# bpod_stepper_1_4_6_teensy32.net
KiCad netlist of a schematic drawn in EAGLE
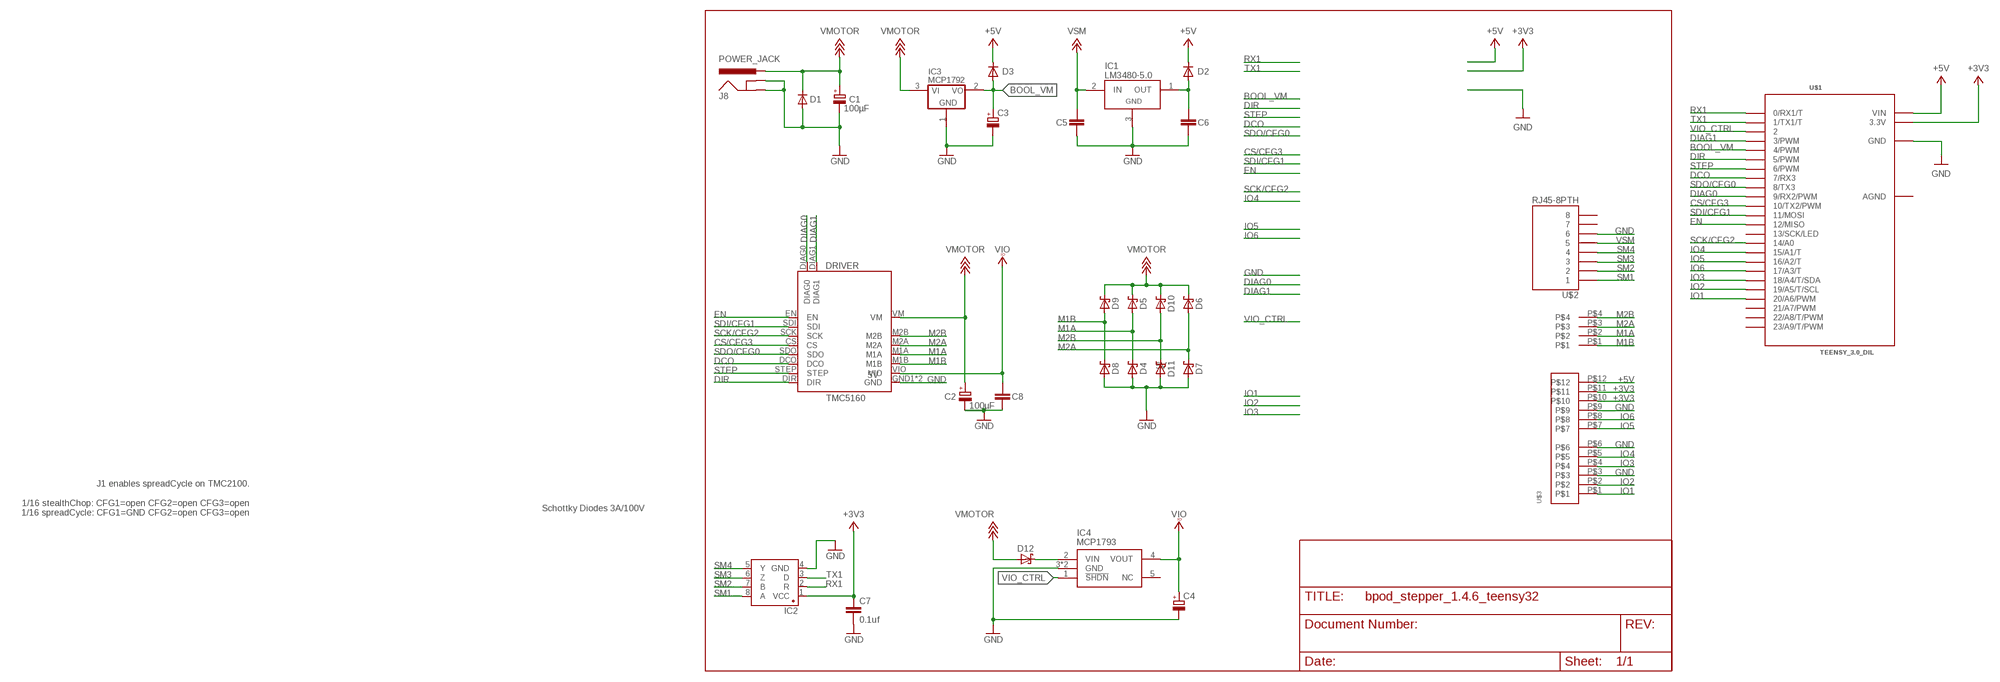
[diagram p0: schematic, sheet 1]

(export (version "E")
  (design (tool "Eeschema 10.0.6"))
  (components
    (comp (ref "C1")
      (value "100µF")
      (footprint "eagle-import:PANASONIC_G")
      (libsource (lib "eagle-import") (part "CPOL-EUG"))
    )
    (comp (ref "C2")
      (value "100µF")
      (footprint "eagle-import:PANASONIC_G")
      (libsource (lib "eagle-import") (part "CPOL-EUG"))
    )
    (comp (ref "C3")
      (value "CPOL-EUB")
      (footprint "eagle-import:PANASONIC_B")
      (libsource (lib "eagle-import") (part "CPOL-EUB"))
    )
    (comp (ref "C4")
      (value "CPOL-EUB")
      (footprint "eagle-import:PANASONIC_B")
      (libsource (lib "eagle-import") (part "CPOL-EUB"))
    )
    (comp (ref "C5")
      (value "0.1uf")
      (footprint "eagle-import:1206@1")
      (libsource (lib "eagle-import") (part "CAP1206"))
    )
    (comp (ref "C6")
      (value "0.1uf")
      (footprint "eagle-import:1206@1")
      (libsource (lib "eagle-import") (part "CAP1206"))
    )
    (comp (ref "C7")
      (value "0.1uf")
      (footprint "eagle-import:1206@1")
      (libsource (lib "eagle-import") (part "CAP1206"))
    )
    (comp (ref "C8")
      (value "100nf")
      (footprint "eagle-import:1206@1")
      (libsource (lib "eagle-import") (part "CAP1206"))
    )
    (comp (ref "D1")
      (value "DIODE-DO214AA")
      (footprint "eagle-import:DO214AA")
      (libsource (lib "eagle-import") (part "DIODE-DO214AA"))
    )
    (comp (ref "D2")
      (value "MBR0520LT")
      (footprint "eagle-import:SOD123")
      (libsource (lib "eagle-import") (part "MBR0520LT"))
    )
    (comp (ref "D3")
      (value "MBR0520LT")
      (footprint "eagle-import:SOD123")
      (libsource (lib "eagle-import") (part "MBR0520LT"))
    )
    (comp (ref "D4")
      (value "S310FA")
      (footprint "eagle-import:SOD123")
      (libsource (lib "eagle-import") (part "D_SCHOTTKY-SOD123"))
    )
    (comp (ref "D5")
      (value "S310FA")
      (footprint "eagle-import:SOD123")
      (libsource (lib "eagle-import") (part "D_SCHOTTKY-SOD123"))
    )
    (comp (ref "D6")
      (value "S310FA")
      (footprint "eagle-import:SOD123")
      (libsource (lib "eagle-import") (part "D_SCHOTTKY-SOD123"))
    )
    (comp (ref "D7")
      (value "S310FA")
      (footprint "eagle-import:SOD123")
      (libsource (lib "eagle-import") (part "D_SCHOTTKY-SOD123"))
    )
    (comp (ref "D8")
      (value "S310FA")
      (footprint "eagle-import:SOD123")
      (libsource (lib "eagle-import") (part "D_SCHOTTKY-SOD123"))
    )
    (comp (ref "D9")
      (value "S310FA")
      (footprint "eagle-import:SOD123")
      (libsource (lib "eagle-import") (part "D_SCHOTTKY-SOD123"))
    )
    (comp (ref "D10")
      (value "S310FA")
      (footprint "eagle-import:SOD123")
      (libsource (lib "eagle-import") (part "D_SCHOTTKY-SOD123"))
    )
    (comp (ref "D11")
      (value "S310FA")
      (footprint "eagle-import:SOD123")
      (libsource (lib "eagle-import") (part "D_SCHOTTKY-SOD123"))
    )
    (comp (ref "D12")
      (value "S310FA")
      (footprint "eagle-import:SOD123")
      (libsource (lib "eagle-import") (part "D_SCHOTTKY-SOD123"))
    )
    (comp (ref "DRIVER")
      (value "TMC5160")
      (footprint "eagle-import:TMC5160")
      (libsource (lib "eagle-import") (part "TMC5160"))
    )
    (comp (ref "IC1")
      (value "LM3480-5.0")
      (footprint "eagle-import:SOT-23-3")
      (libsource (lib "eagle-import") (part "LM3480-5.0"))
    )
    (comp (ref "IC2")
      (value "SN65HVD31DR")
      (footprint "eagle-import:SO08")
      (libsource (lib "eagle-import") (part "SN65HVD31DR"))
    )
    (comp (ref "IC3")
      (value "MCP1792")
      (footprint "eagle-import:SOT23A_MICROCHIP_CB")
      (libsource (lib "eagle-import") (part "MCP170302E/CB-12"))
    )
    (comp (ref "IC4")
      (value "MCP1793")
      (footprint "eagle-import:SOT223-5")
      (libsource (lib "eagle-import") (part "MCP1793_SOT223-5"))
    )
    (comp (ref "J8")
      (value "POWER_JACK")
      (footprint "eagle-import:POWER_JACK_PTH")
      (libsource (lib "eagle-import") (part "POWER_JACK"))
    )
    (comp (ref "U$1")
      (value "TEENSY_3.0_DIL")
      (footprint "eagle-import:TEENSY_3.0-3.2&LC_DIL")
      (libsource (lib "eagle-import") (part "TEENSY_3.0_DIL"))
    )
    (comp (ref "U$2")
      (value "RJ45-8PTH")
      (footprint "eagle-import:RJ45-8")
      (libsource (lib "eagle-import") (part "RJ45-8PTH"))
    )
    (comp (ref "U$3")
      (value "12POS_MOLEX_SOCKET")
      (footprint "eagle-import:12POS_MOLEX_SOCKET")
      (libsource (lib "eagle-import") (part "12POS_MOLEX_SOCKET"))
    )
    (comp (ref "U$4")
      (value "MOLEX395221004")
      (footprint "eagle-import:MOLEX395221004")
      (libsource (lib "eagle-import") (part "MOLEX395221004"))
    )
  )
  (nets
    (net (code "1") (name "+3V3") (class "Default")
      (node (ref "C7") (pin "1") (pinfunction "1_1") (pintype "passive"))
      (node (ref "IC2") (pin "1") (pinfunction "VCC_1") (pintype "bidirectional"))
      (node (ref "U$1") (pin "3.3V") (pinfunction "3.3V_3.3V") (pintype "power_in"))
      (node (ref "U$3") (pin "P$10") (pinfunction "P$10_P$10") (pintype "bidirectional"))
      (node (ref "U$3") (pin "P$11") (pinfunction "P$11_P$11") (pintype "bidirectional"))
    )
    (net (code "2") (name "+5V") (class "Default")
      (node (ref "D2") (pin "C") (pinfunction "C_C") (pintype "passive"))
      (node (ref "D3") (pin "C") (pinfunction "C_C") (pintype "passive"))
      (node (ref "U$1") (pin "VIN") (pinfunction "VIN_VIN") (pintype "power_in"))
      (node (ref "U$3") (pin "P$12") (pinfunction "P$12_P$12") (pintype "bidirectional"))
    )
    (net (code "3") (name "+12V") (class "Default")
      (node (ref "C5") (pin "2") (pinfunction "2_2") (pintype "passive"))
      (node (ref "IC1") (pin "2") (pinfunction "IN_2") (pintype "power_in"))
      (node (ref "U$2") (pin "5") (pinfunction "5_5") (pintype "bidirectional"))
    )
    (net (code "4") (name "+18V") (class "Default")
      (node (ref "C1") (pin "+") (pinfunction "+_+") (pintype "passive"))
      (node (ref "C2") (pin "+") (pinfunction "+_+") (pintype "passive"))
      (node (ref "D1") (pin "C") (pinfunction "C_C") (pintype "passive"))
      (node (ref "D10") (pin "C") (pinfunction "C_C") (pintype "passive"))
      (node (ref "D12") (pin "A") (pinfunction "A_A") (pintype "passive"))
      (node (ref "D5") (pin "C") (pinfunction "C_C") (pintype "passive"))
      (node (ref "D6") (pin "C") (pinfunction "C_C") (pintype "passive"))
      (node (ref "D9") (pin "C") (pinfunction "C_C") (pintype "passive"))
      (node (ref "DRIVER") (pin "VM") (pinfunction "VM_VM") (pintype "power_in"))
      (node (ref "IC3") (pin "3") (pinfunction "VI_3") (pintype "power_in"))
      (node (ref "J8") (pin "PWR") (pinfunction "PWR_PWR") (pintype "bidirectional"))
    )
    (net (code "5") (name "/AGND") (class "Default")
      (node (ref "U$1") (pin "AGND") (pinfunction "AGND_AGND") (pintype "power_in"))
    )
    (net (code "6") (name "/CS{slash}CFG3") (class "Default")
      (node (ref "DRIVER") (pin "CS") (pinfunction "CS_CS") (pintype "passive"))
      (node (ref "U$1") (pin "10") (pinfunction "10/TX2/PWM_10") (pintype "bidirectional"))
    )
    (net (code "7") (name "/DCO") (class "Default")
      (node (ref "DRIVER") (pin "DCO") (pinfunction "DCO_DCO") (pintype "passive"))
      (node (ref "U$1") (pin "7") (pinfunction "7/RX3_7") (pintype "bidirectional"))
    )
    (net (code "8") (name "/DIAG0") (class "Default")
      (node (ref "DRIVER") (pin "DIAG0") (pinfunction "DIAG0_DIAG0") (pintype "passive"))
      (node (ref "U$1") (pin "9") (pinfunction "9/RX2/PWM_9") (pintype "bidirectional"))
    )
    (net (code "9") (name "/DIAG1") (class "Default")
      (node (ref "DRIVER") (pin "DIAG1") (pinfunction "DIAG1_DIAG1") (pintype "passive"))
      (node (ref "U$1") (pin "3") (pinfunction "3/PWM_3") (pintype "bidirectional"))
    )
    (net (code "10") (name "/DIR") (class "Default")
      (node (ref "DRIVER") (pin "DIR") (pinfunction "DIR_DIR") (pintype "input"))
      (node (ref "U$1") (pin "5") (pinfunction "5/PWM_5") (pintype "bidirectional"))
    )
    (net (code "11") (name "/EN") (class "Default")
      (node (ref "DRIVER") (pin "EN") (pinfunction "EN_EN") (pintype "passive"))
      (node (ref "U$1") (pin "12") (pinfunction "12/MISO_12") (pintype "bidirectional"))
    )
    (net (code "12") (name "/IO1") (class "Default")
      (node (ref "U$1") (pin "20/A6") (pinfunction "20/A6/PWM_20/A6") (pintype "bidirectional"))
      (node (ref "U$3") (pin "P$1") (pinfunction "P$1_P$1") (pintype "bidirectional"))
    )
    (net (code "13") (name "/IO2") (class "Default")
      (node (ref "U$1") (pin "19/A5") (pinfunction "19/A5/T/SCL_19/A5") (pintype "bidirectional"))
      (node (ref "U$3") (pin "P$2") (pinfunction "P$2_P$2") (pintype "bidirectional"))
    )
    (net (code "14") (name "/IO3") (class "Default")
      (node (ref "U$1") (pin "18/A4") (pinfunction "18/A4/T/SDA_18/A4") (pintype "bidirectional"))
      (node (ref "U$3") (pin "P$4") (pinfunction "P$4_P$4") (pintype "bidirectional"))
    )
    (net (code "15") (name "/IO4") (class "Default")
      (node (ref "U$1") (pin "15/A1") (pinfunction "15/A1/T_15/A1") (pintype "bidirectional"))
      (node (ref "U$3") (pin "P$5") (pinfunction "P$5_P$5") (pintype "bidirectional"))
    )
    (net (code "16") (name "/IO5") (class "Default")
      (node (ref "U$1") (pin "16/A2") (pinfunction "16/A2/T_16/A2") (pintype "bidirectional"))
      (node (ref "U$3") (pin "P$7") (pinfunction "P$7_P$7") (pintype "bidirectional"))
    )
    (net (code "17") (name "/IO6") (class "Default")
      (node (ref "U$1") (pin "17/A3") (pinfunction "17/A3/T_17/A3") (pintype "bidirectional"))
      (node (ref "U$3") (pin "P$8") (pinfunction "P$8_P$8") (pintype "bidirectional"))
    )
    (net (code "18") (name "/M1A") (class "Default")
      (node (ref "D4") (pin "C") (pinfunction "C_C") (pintype "passive"))
      (node (ref "D5") (pin "A") (pinfunction "A_A") (pintype "passive"))
      (node (ref "DRIVER") (pin "M1A") (pinfunction "M1A_M1A") (pintype "output"))
      (node (ref "U$4") (pin "P$2") (pinfunction "P$2_P$2") (pintype "bidirectional"))
    )
    (net (code "19") (name "/M1B") (class "Default")
      (node (ref "D8") (pin "C") (pinfunction "C_C") (pintype "passive"))
      (node (ref "D9") (pin "A") (pinfunction "A_A") (pintype "passive"))
      (node (ref "DRIVER") (pin "M1B") (pinfunction "M1B_M1B") (pintype "output"))
      (node (ref "U$4") (pin "P$1") (pinfunction "P$1_P$1") (pintype "bidirectional"))
    )
    (net (code "20") (name "/M2A") (class "Default")
      (node (ref "D6") (pin "A") (pinfunction "A_A") (pintype "passive"))
      (node (ref "D7") (pin "C") (pinfunction "C_C") (pintype "passive"))
      (node (ref "DRIVER") (pin "M2A") (pinfunction "M2A_M2A") (pintype "output"))
      (node (ref "U$4") (pin "P$3") (pinfunction "P$3_P$3") (pintype "bidirectional"))
    )
    (net (code "21") (name "/M2B") (class "Default")
      (node (ref "D10") (pin "A") (pinfunction "A_A") (pintype "passive"))
      (node (ref "D11") (pin "C") (pinfunction "C_C") (pintype "passive"))
      (node (ref "DRIVER") (pin "M2B") (pinfunction "M2B_M2B") (pintype "output"))
      (node (ref "U$4") (pin "P$4") (pinfunction "P$4_P$4") (pintype "bidirectional"))
    )
    (net (code "22") (name "/RX1") (class "Default")
      (node (ref "IC2") (pin "2") (pinfunction "R_2") (pintype "bidirectional"))
      (node (ref "U$1") (pin "0") (pinfunction "0/RX1/T_0") (pintype "bidirectional"))
    )
    (net (code "23") (name "/SCK{slash}CFG2") (class "Default")
      (node (ref "DRIVER") (pin "SCK") (pinfunction "SCK_SCK") (pintype "passive"))
      (node (ref "U$1") (pin "14/A0") (pinfunction "14/A0_14/A0") (pintype "bidirectional"))
    )
    (net (code "24") (name "/SDI{slash}CFG1") (class "Default")
      (node (ref "DRIVER") (pin "SDI") (pinfunction "SDI_SDI") (pintype "passive"))
      (node (ref "U$1") (pin "11") (pinfunction "11/MOSI_11") (pintype "bidirectional"))
    )
    (net (code "25") (name "/SDO{slash}CFG0") (class "Default")
      (node (ref "DRIVER") (pin "SDO") (pinfunction "SDO_SDO") (pintype "passive"))
      (node (ref "U$1") (pin "8") (pinfunction "8/TX3_8") (pintype "bidirectional"))
    )
    (net (code "26") (name "/SM1") (class "Default")
      (node (ref "IC2") (pin "8") (pinfunction "A_8") (pintype "bidirectional"))
      (node (ref "U$2") (pin "1") (pinfunction "1_1") (pintype "bidirectional"))
    )
    (net (code "27") (name "/SM2") (class "Default")
      (node (ref "IC2") (pin "7") (pinfunction "B_7") (pintype "bidirectional"))
      (node (ref "U$2") (pin "2") (pinfunction "2_2") (pintype "bidirectional"))
    )
    (net (code "28") (name "/SM3") (class "Default")
      (node (ref "IC2") (pin "6") (pinfunction "Z_6") (pintype "bidirectional"))
      (node (ref "U$2") (pin "3") (pinfunction "3_3") (pintype "bidirectional"))
    )
    (net (code "29") (name "/SM4") (class "Default")
      (node (ref "IC2") (pin "5") (pinfunction "Y_5") (pintype "bidirectional"))
      (node (ref "U$2") (pin "4") (pinfunction "4_4") (pintype "bidirectional"))
    )
    (net (code "30") (name "/STEP") (class "Default")
      (node (ref "DRIVER") (pin "STEP") (pinfunction "STEP_STEP") (pintype "input"))
      (node (ref "U$1") (pin "6") (pinfunction "6/PWM_6") (pintype "bidirectional"))
    )
    (net (code "31") (name "/TX1") (class "Default")
      (node (ref "IC2") (pin "3") (pinfunction "D_3") (pintype "bidirectional"))
      (node (ref "U$1") (pin "1") (pinfunction "1/TX1/T_1") (pintype "bidirectional"))
    )
    (net (code "32") (name "BOOL_VM") (class "Default")
      (node (ref "C3") (pin "+") (pinfunction "+_+") (pintype "passive"))
      (node (ref "D3") (pin "A") (pinfunction "A_A") (pintype "passive"))
      (node (ref "IC3") (pin "2") (pinfunction "VO_2") (pintype "passive"))
      (node (ref "U$1") (pin "4") (pinfunction "4/PWM_4") (pintype "bidirectional"))
    )
    (net (code "33") (name "GND") (class "Default")
      (node (ref "C1") (pin "-") (pinfunction "-_-") (pintype "passive"))
      (node (ref "C2") (pin "-") (pinfunction "-_-") (pintype "passive"))
      (node (ref "C3") (pin "-") (pinfunction "-_-") (pintype "passive"))
      (node (ref "C4") (pin "-") (pinfunction "-_-") (pintype "passive"))
      (node (ref "C5") (pin "1") (pinfunction "1_1") (pintype "passive"))
      (node (ref "C6") (pin "1") (pinfunction "1_1") (pintype "passive"))
      (node (ref "C7") (pin "2") (pinfunction "2_2") (pintype "passive"))
      (node (ref "C8") (pin "2") (pinfunction "2_2") (pintype "passive"))
      (node (ref "D1") (pin "A") (pinfunction "A_A") (pintype "passive"))
      (node (ref "D11") (pin "A") (pinfunction "A_A") (pintype "passive"))
      (node (ref "D4") (pin "A") (pinfunction "A_A") (pintype "passive"))
      (node (ref "D7") (pin "A") (pinfunction "A_A") (pintype "passive"))
      (node (ref "D8") (pin "A") (pinfunction "A_A") (pintype "passive"))
      (node (ref "DRIVER") (pin "GND1") (pinfunction "GND_GND1") (pintype "power_in"))
      (node (ref "DRIVER") (pin "GND2") (pinfunction "GND_GND2") (pintype "power_in"))
      (node (ref "IC1") (pin "3") (pinfunction "GND_3") (pintype "power_in"))
      (node (ref "IC2") (pin "4") (pinfunction "GND_4") (pintype "bidirectional"))
      (node (ref "IC3") (pin "1") (pinfunction "GND_1") (pintype "power_in"))
      (node (ref "IC4") (pin "3") (pinfunction "GND_3") (pintype "bidirectional"))
      (node (ref "IC4") (pin "6") (pinfunction "GND_6") (pintype "bidirectional"))
      (node (ref "J8") (pin "GND") (pinfunction "GND_GND") (pintype "bidirectional"))
      (node (ref "J8") (pin "GNDBREAK") (pinfunction "GNDBREAK_GNDBREAK") (pintype "bidirectional"))
      (node (ref "U$1") (pin "GND") (pinfunction "GND_GND") (pintype "power_in"))
      (node (ref "U$2") (pin "6") (pinfunction "6_6") (pintype "bidirectional"))
      (node (ref "U$3") (pin "P$3") (pinfunction "P$3_P$3") (pintype "bidirectional"))
      (node (ref "U$3") (pin "P$6") (pinfunction "P$6_P$6") (pintype "bidirectional"))
      (node (ref "U$3") (pin "P$9") (pinfunction "P$9_P$9") (pintype "bidirectional"))
    )
    (net (code "34") (name "Net-(IC1-OUT)") (class "Default")
      (node (ref "C6") (pin "2") (pinfunction "2_2") (pintype "passive"))
      (node (ref "D2") (pin "A") (pinfunction "A_A") (pintype "passive"))
      (node (ref "IC1") (pin "1") (pinfunction "OUT_1") (pintype "power_in"))
    )
    (net (code "35") (name "Net-(IC4-VIN)") (class "Default")
      (node (ref "D12") (pin "C") (pinfunction "C_C") (pintype "passive"))
      (node (ref "IC4") (pin "2") (pinfunction "VIN_2") (pintype "bidirectional"))
    )
    (net (code "36") (name "VCCIO") (class "Default")
      (node (ref "C4") (pin "+") (pinfunction "+_+") (pintype "passive"))
      (node (ref "C8") (pin "1") (pinfunction "1_1") (pintype "passive"))
      (node (ref "DRIVER") (pin "VIO") (pinfunction "VIO_VIO") (pintype "power_in"))
      (node (ref "IC4") (pin "4") (pinfunction "VOUT_4") (pintype "bidirectional"))
    )
    (net (code "37") (name "VIO_CTRL") (class "Default")
      (node (ref "IC4") (pin "1") (pinfunction "~{SHDN}_1") (pintype "bidirectional"))
      (node (ref "U$1") (pin "2") (pinfunction "2_2") (pintype "bidirectional"))
    )
    (net (code "38") (name "unconnected-(IC4-NC-Pad5)") (class "Default")
      (node (ref "IC4") (pin "5") (pinfunction "NC_5") (pintype "bidirectional"))
    )
    (net (code "39") (name "unconnected-(U$1-13{slash}SCK{slash}LED-Pad13)") (class "Default")
      (node (ref "U$1") (pin "13") (pinfunction "13/SCK/LED_13") (pintype "bidirectional"))
    )
    (net (code "40") (name "unconnected-(U$1-21{slash}A7{slash}PWM-Pad21{slash}A7)") (class "Default")
      (node (ref "U$1") (pin "21/A7") (pinfunction "21/A7/PWM_21/A7") (pintype "bidirectional"))
    )
    (net (code "41") (name "unconnected-(U$1-22{slash}A8{slash}T{slash}PWM-Pad22{slash}A8)") (class "Default")
      (node (ref "U$1") (pin "22/A8") (pinfunction "22/A8/T/PWM_22/A8") (pintype "bidirectional"))
    )
    (net (code "42") (name "unconnected-(U$1-23{slash}A9{slash}T{slash}PWM-Pad23{slash}A9)") (class "Default")
      (node (ref "U$1") (pin "23/A9") (pinfunction "23/A9/T/PWM_23/A9") (pintype "bidirectional"))
    )
    (net (code "43") (name "unconnected-(U$2-Pad7)") (class "Default")
      (node (ref "U$2") (pin "7") (pinfunction "7_7") (pintype "bidirectional"))
    )
    (net (code "44") (name "unconnected-(U$2-Pad8)") (class "Default")
      (node (ref "U$2") (pin "8") (pinfunction "8_8") (pintype "bidirectional"))
    )
  )
)
